# 519_jetson_nano_2GB020000.net
KiCad netlist of a schematic drawn in EAGLE
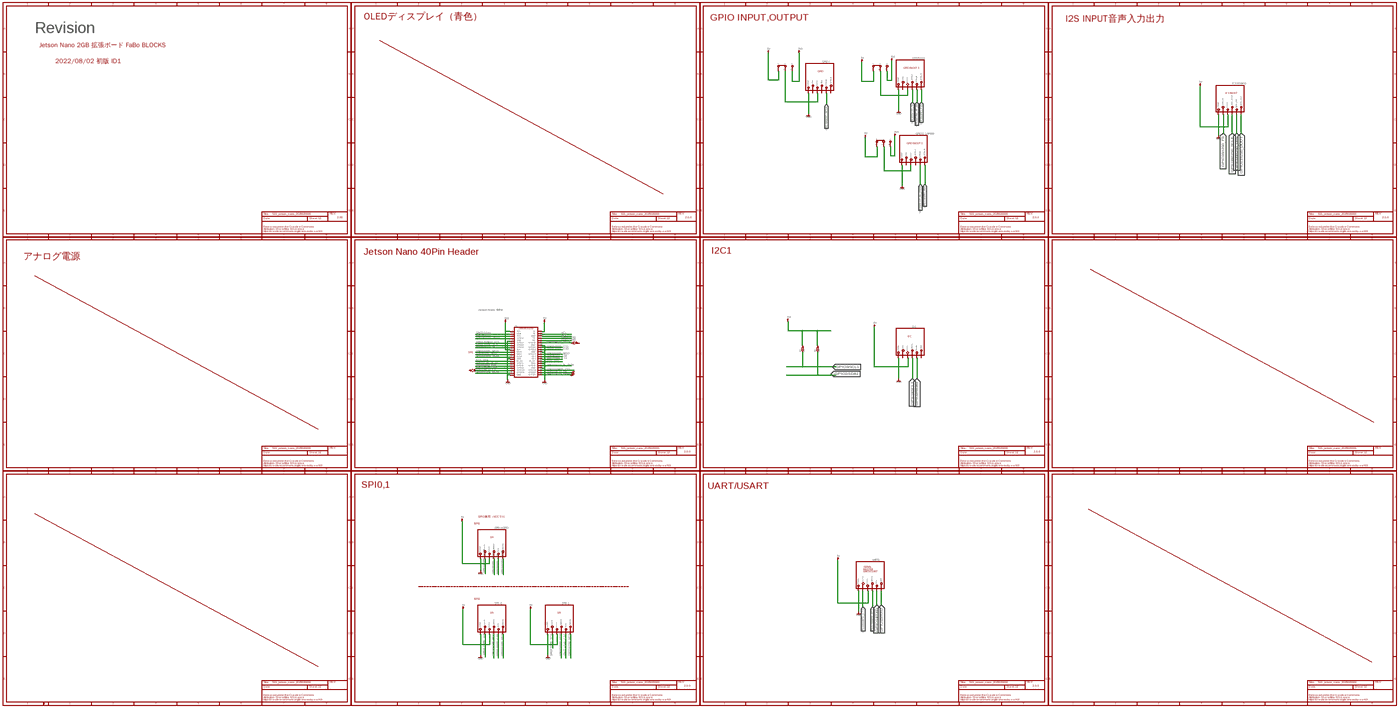
[diagram p0: schematic, sheet 1, overview]
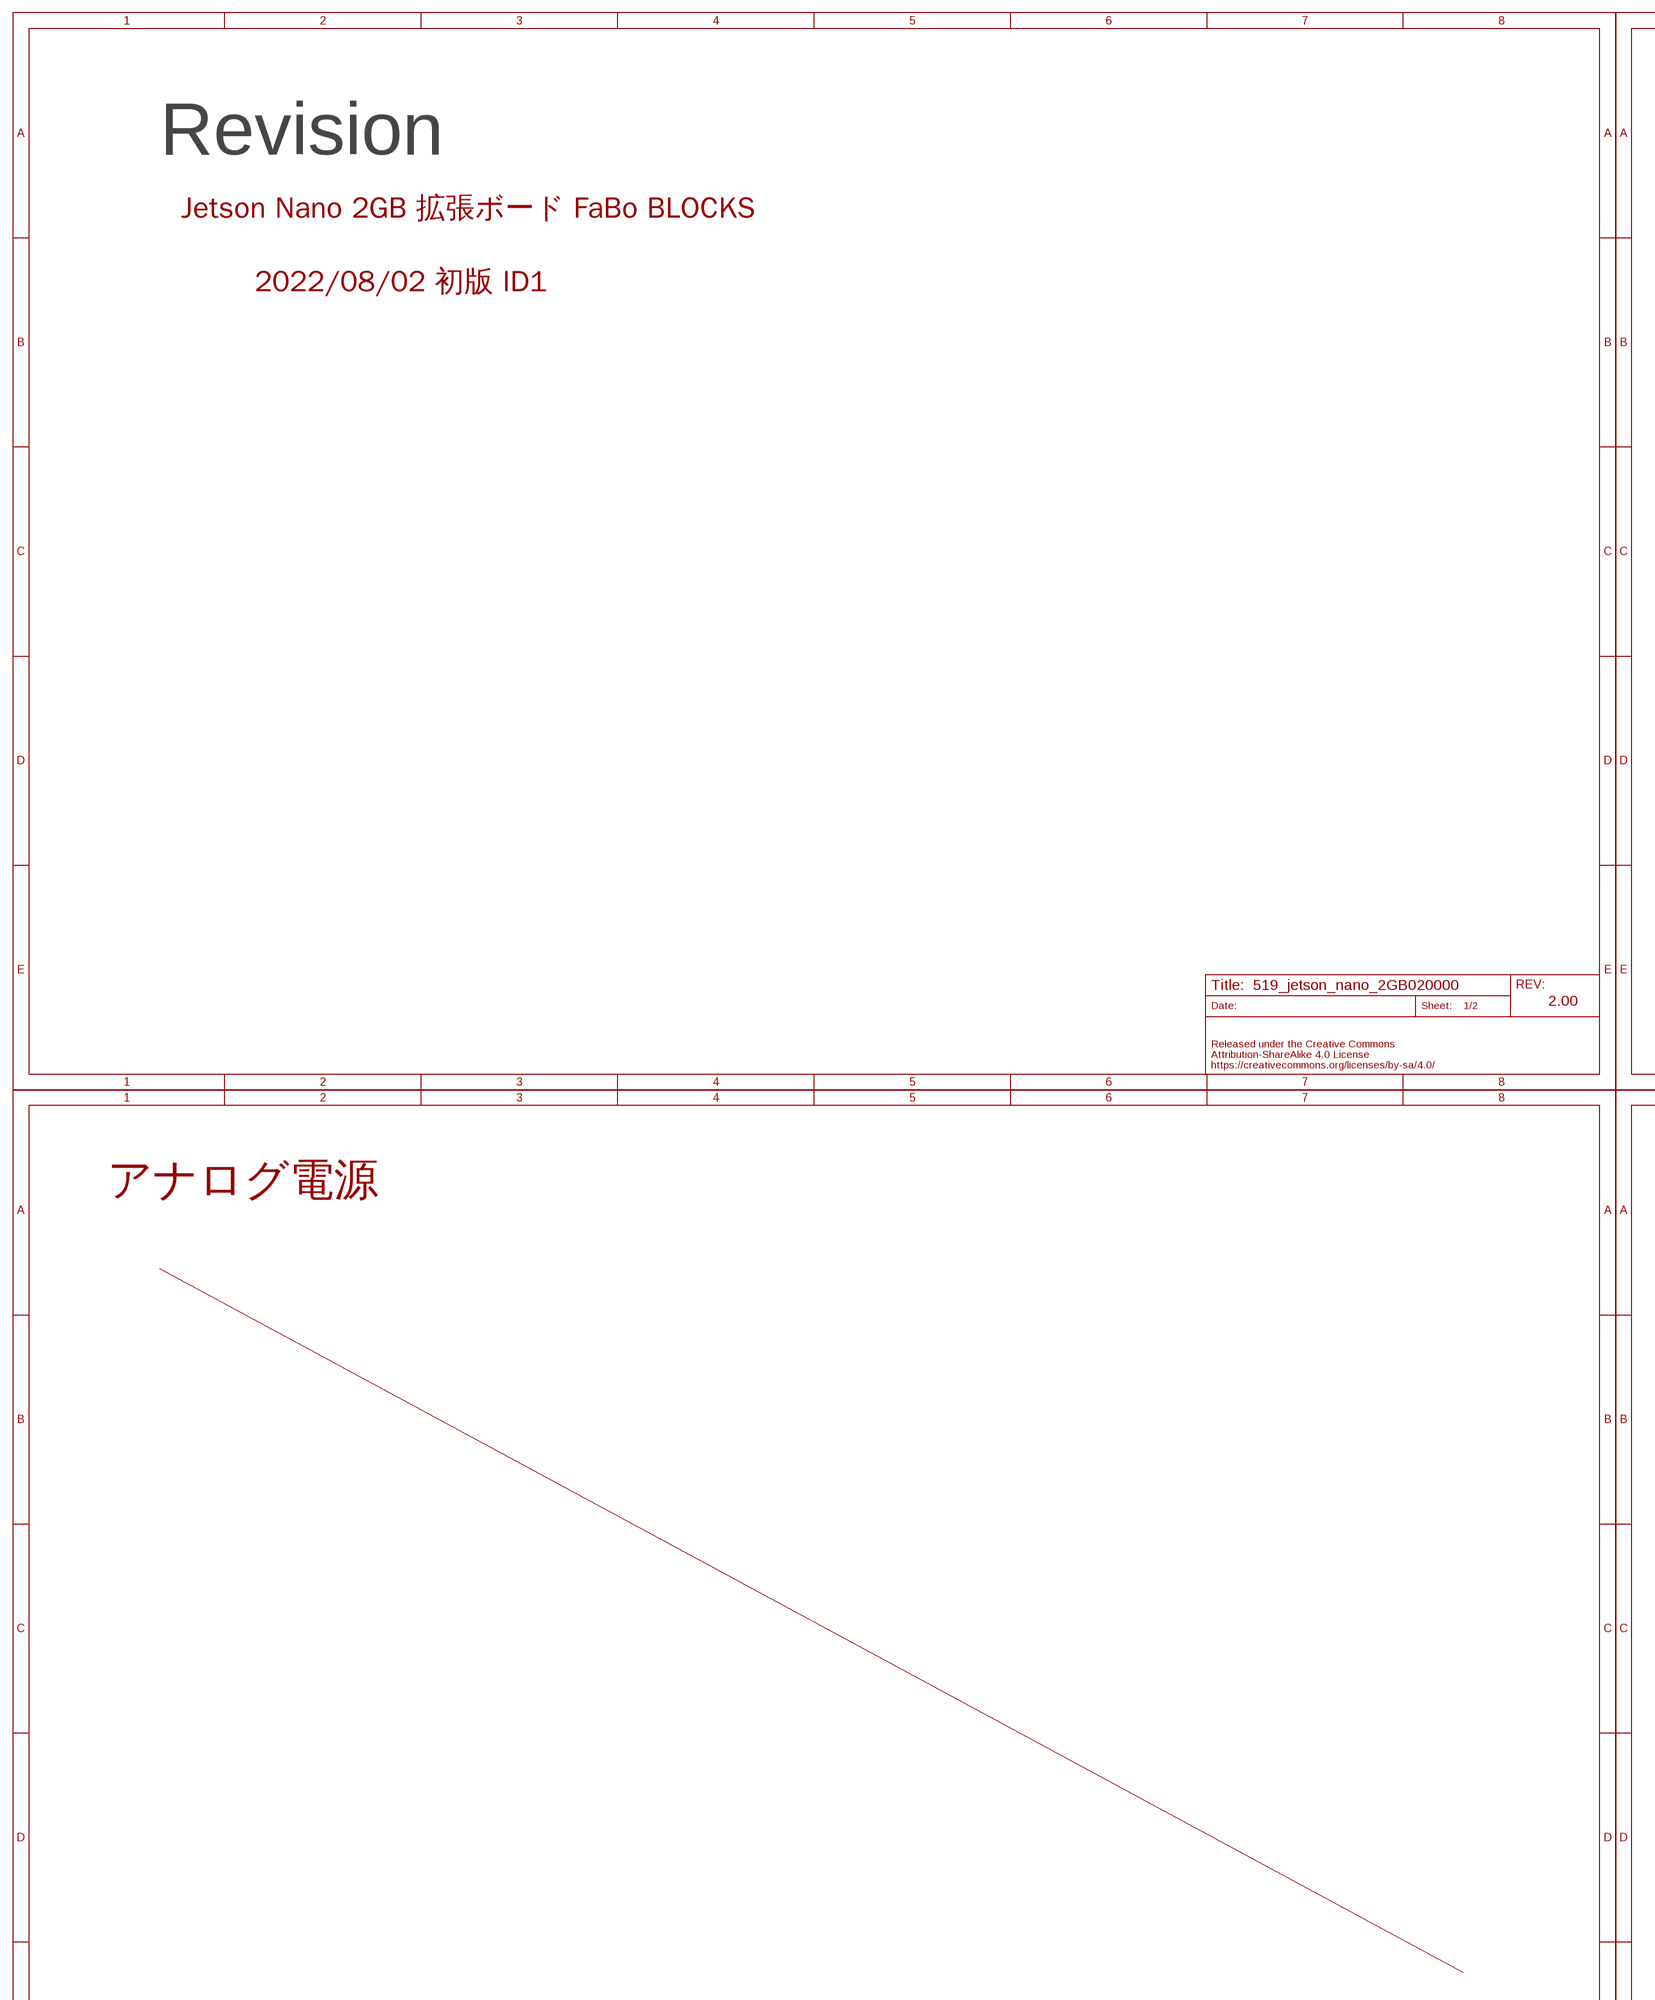
[diagram p1: schematic, sheet 1, part 1 of 6]
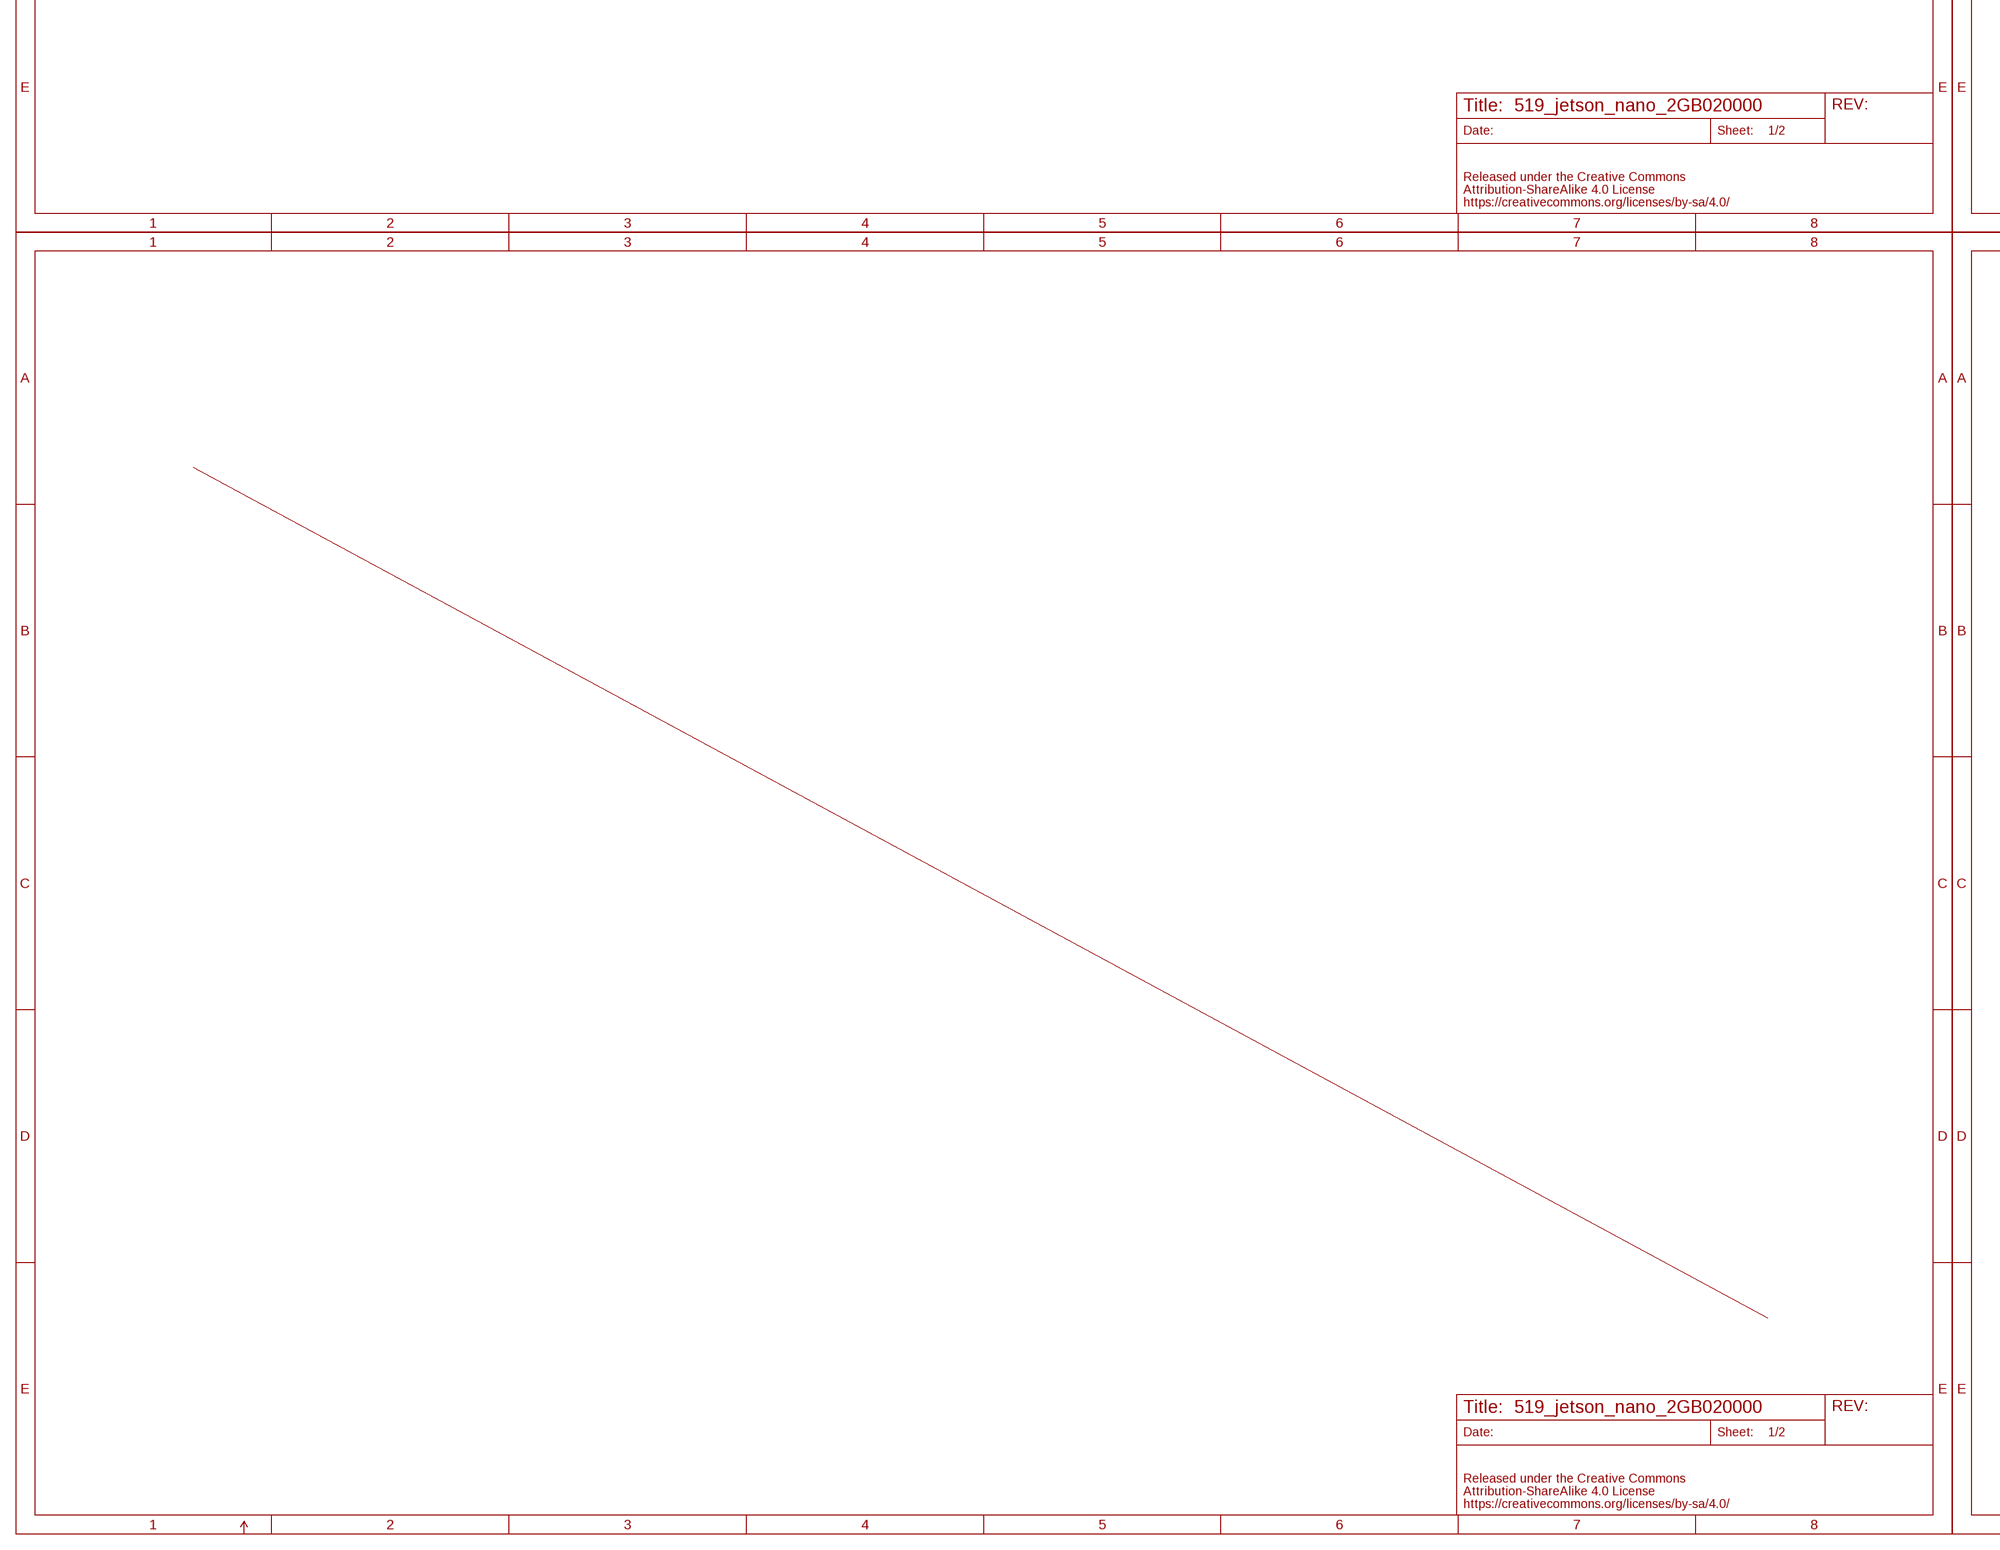
[diagram p2: schematic, sheet 1, part 2 of 6]
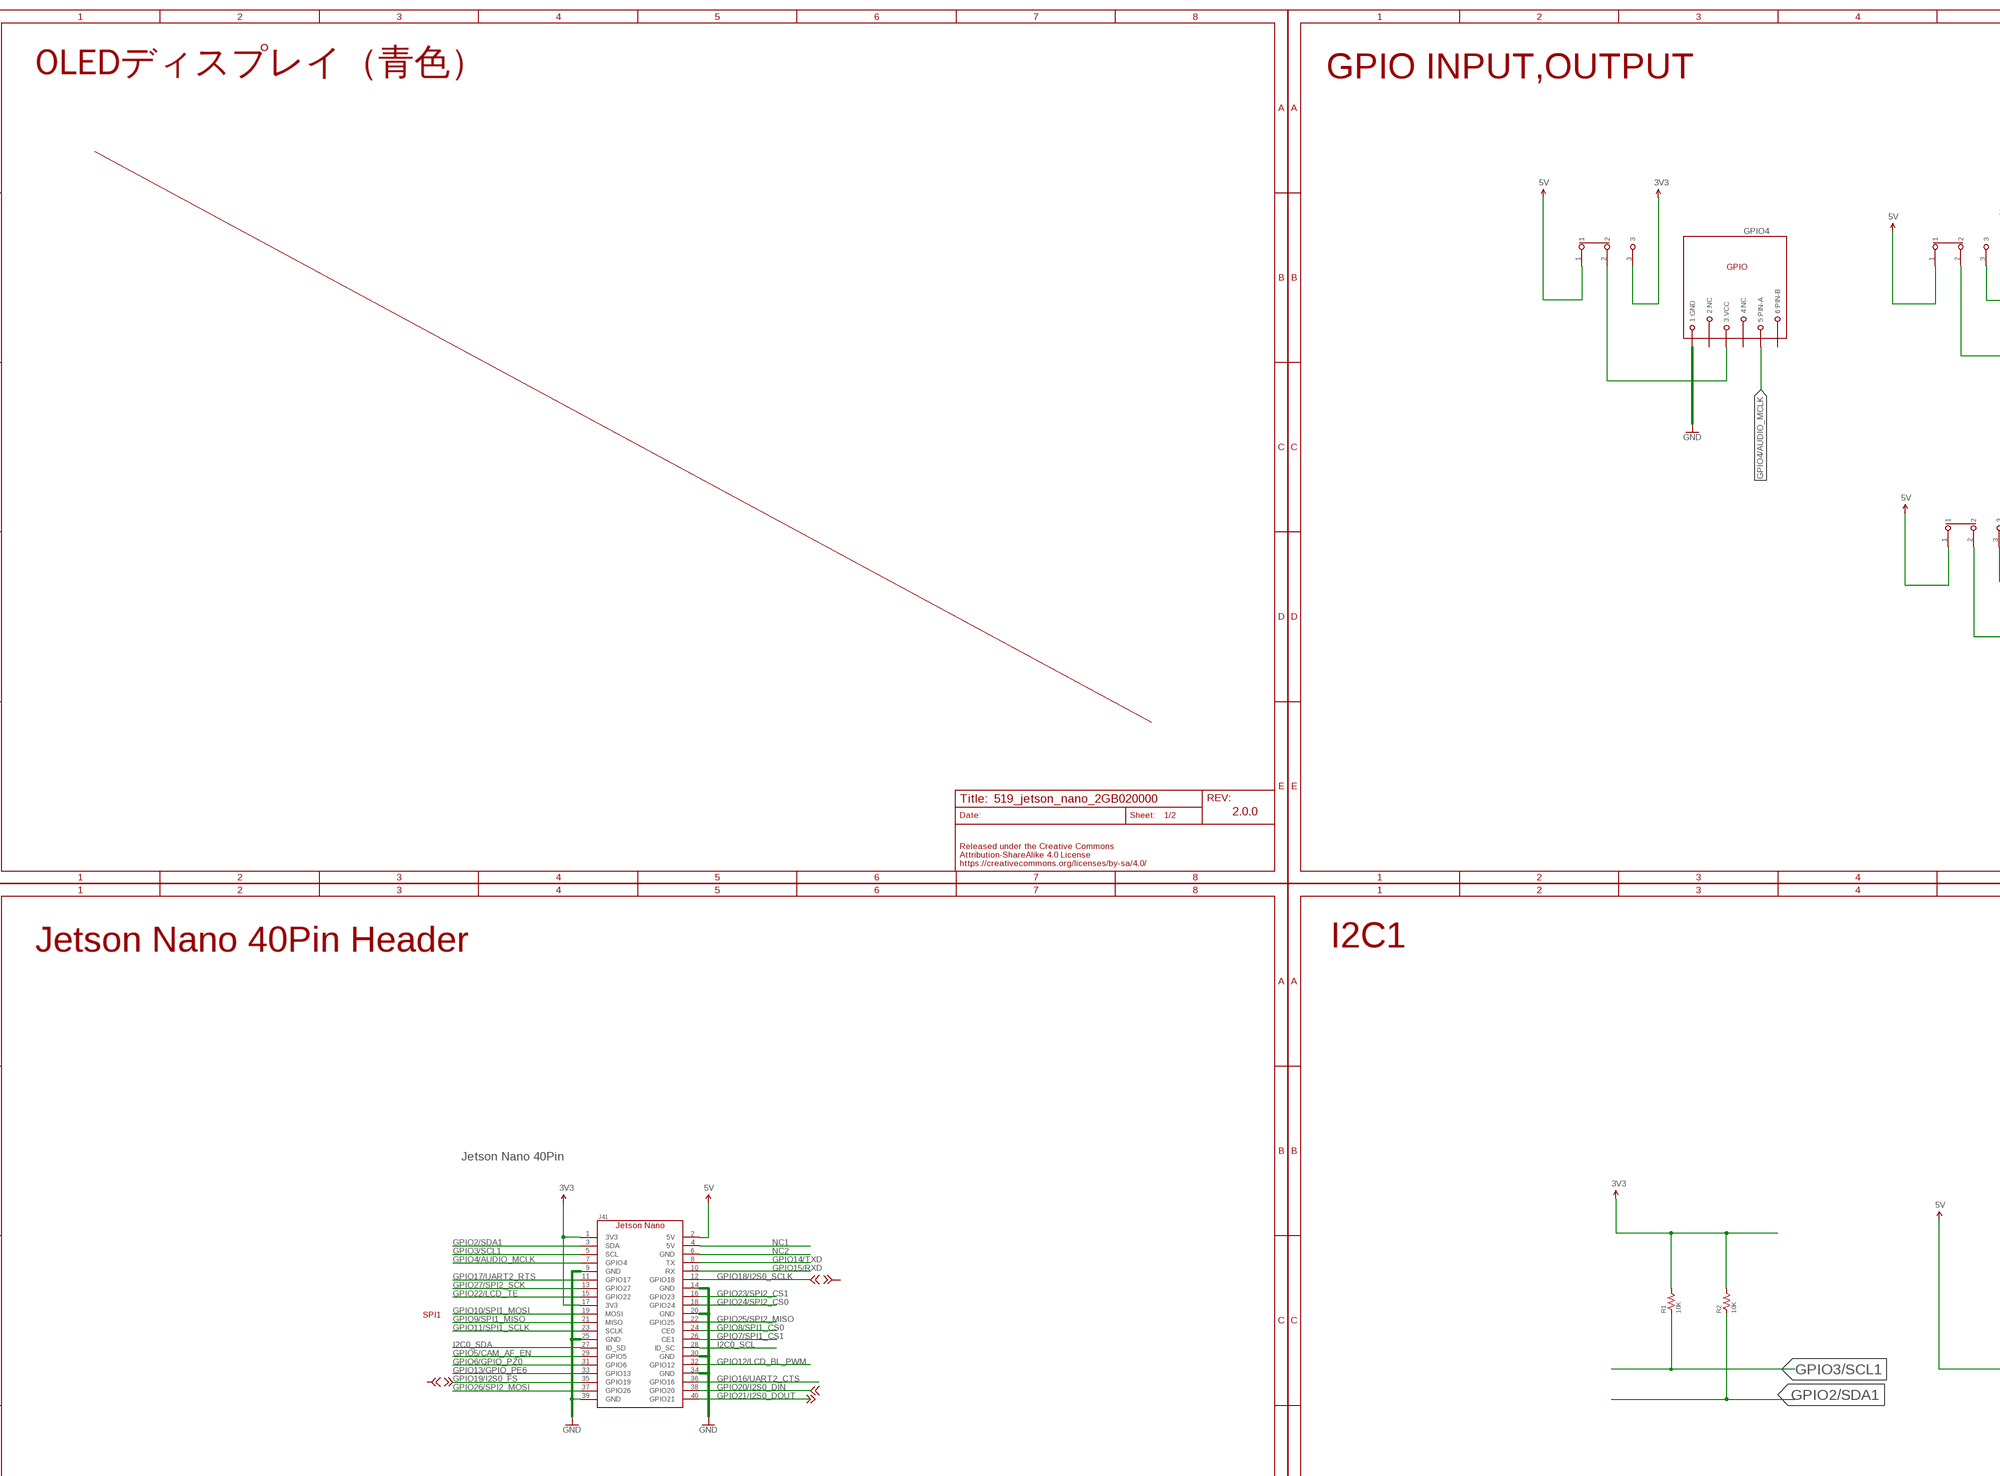
[diagram p3: schematic, sheet 1, part 3 of 6]
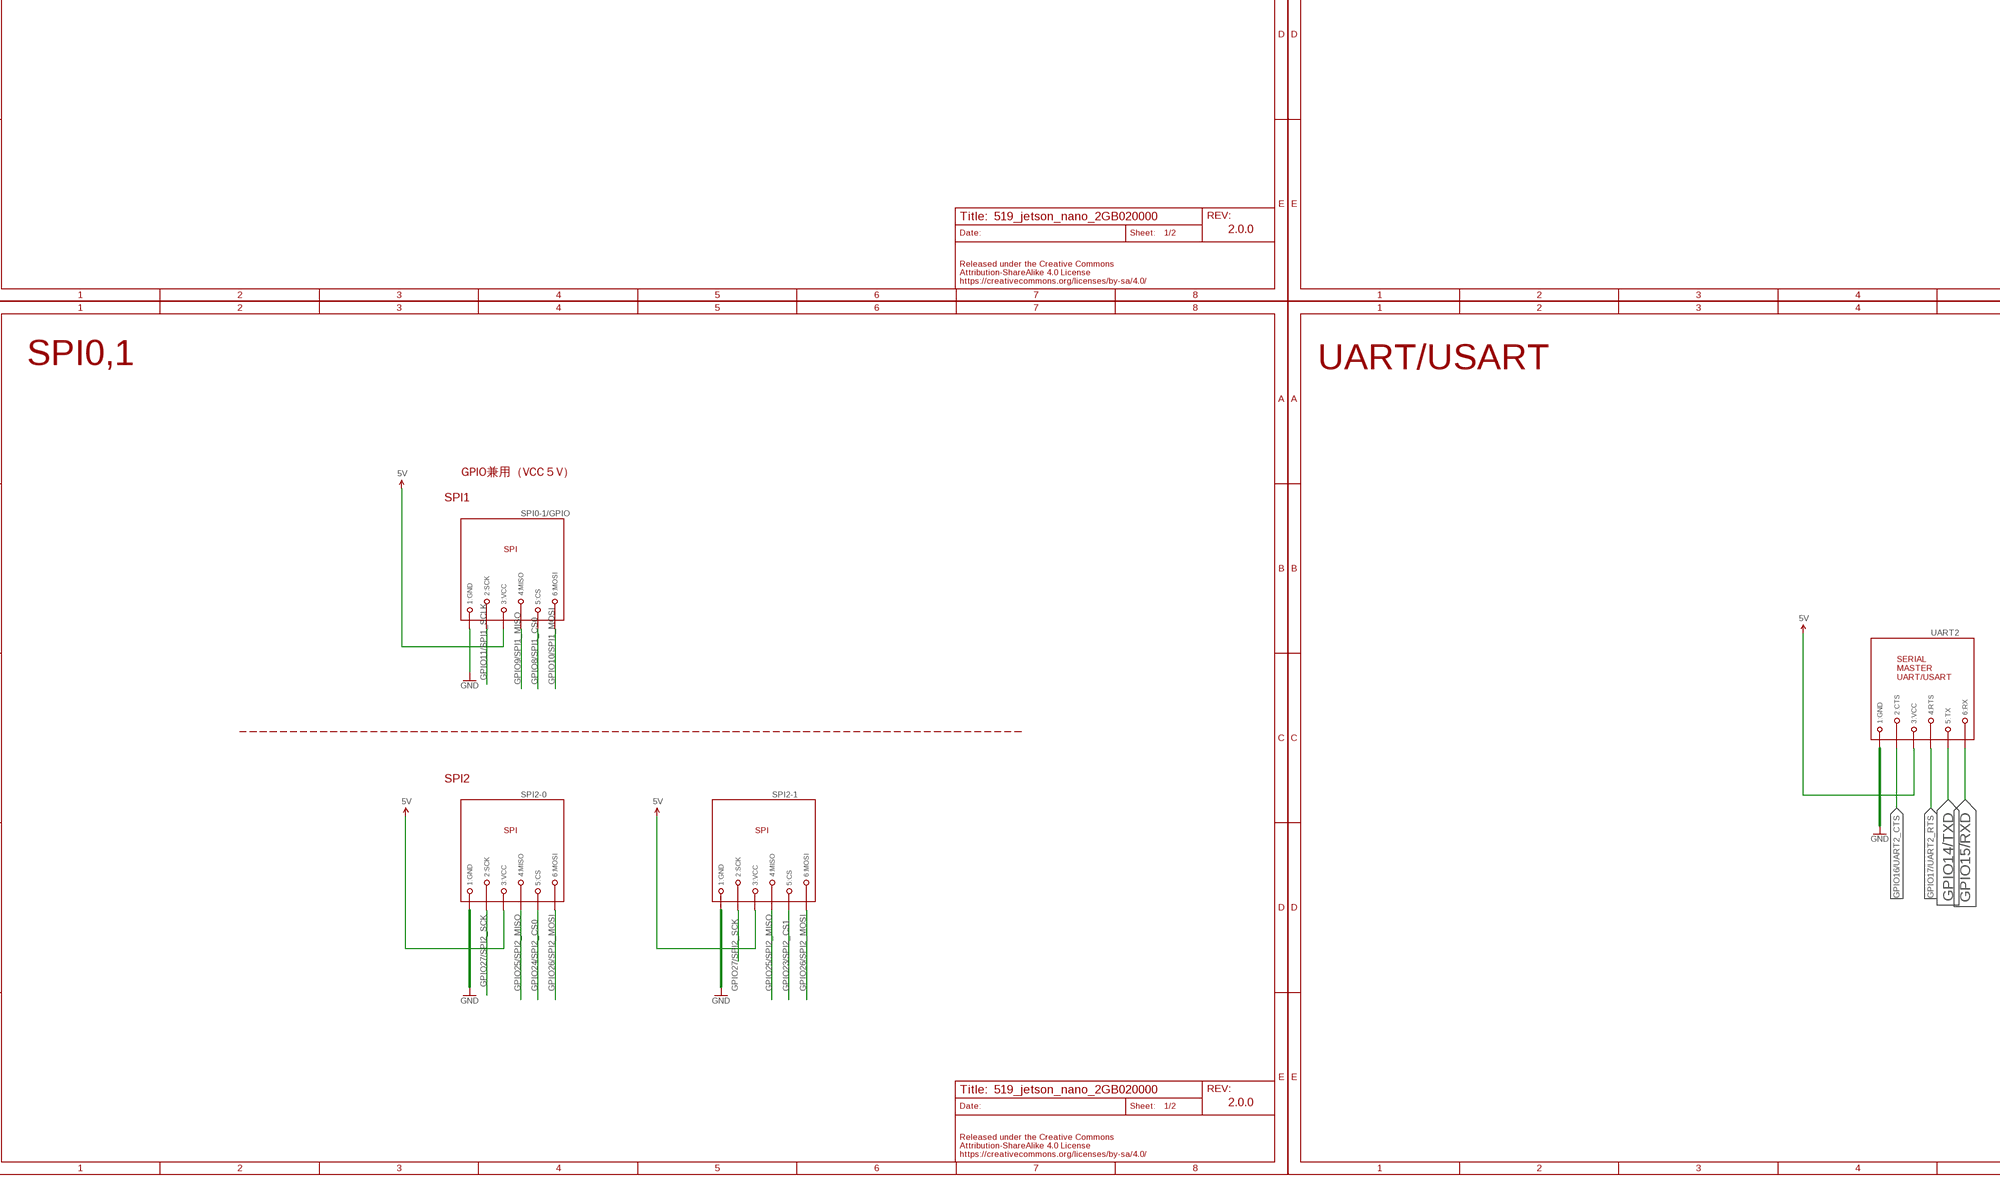
[diagram p4: schematic, sheet 1, part 4 of 6]
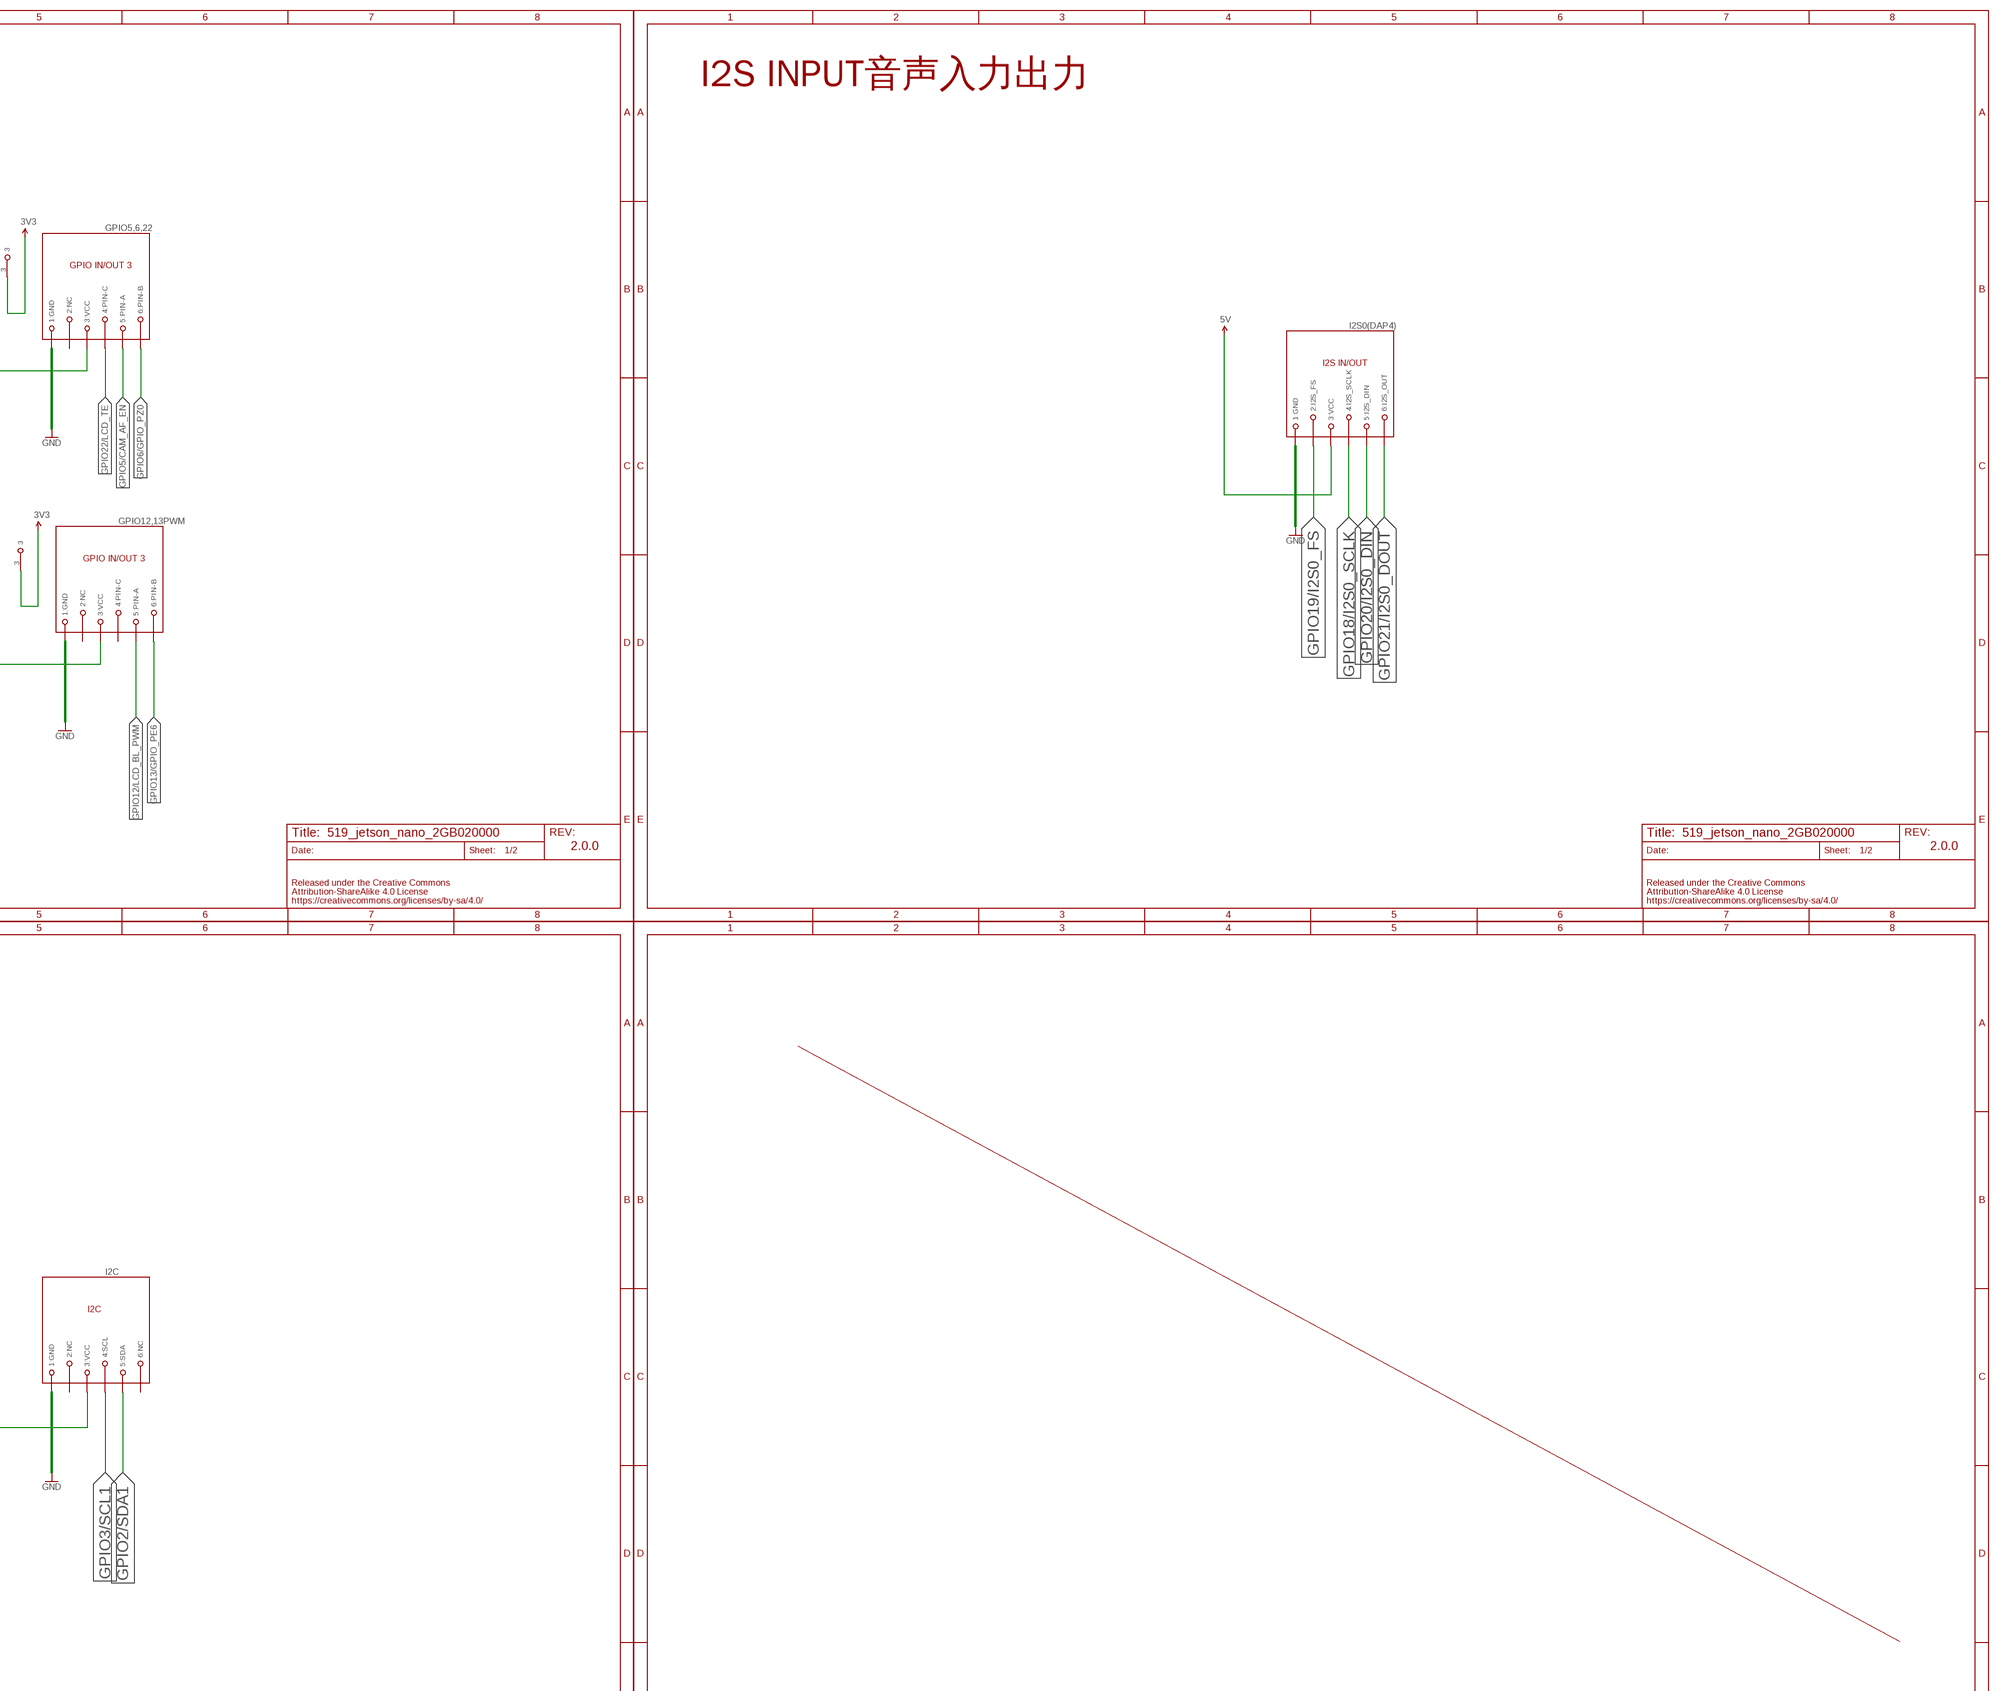
[diagram p5: schematic, sheet 1, part 5 of 6]
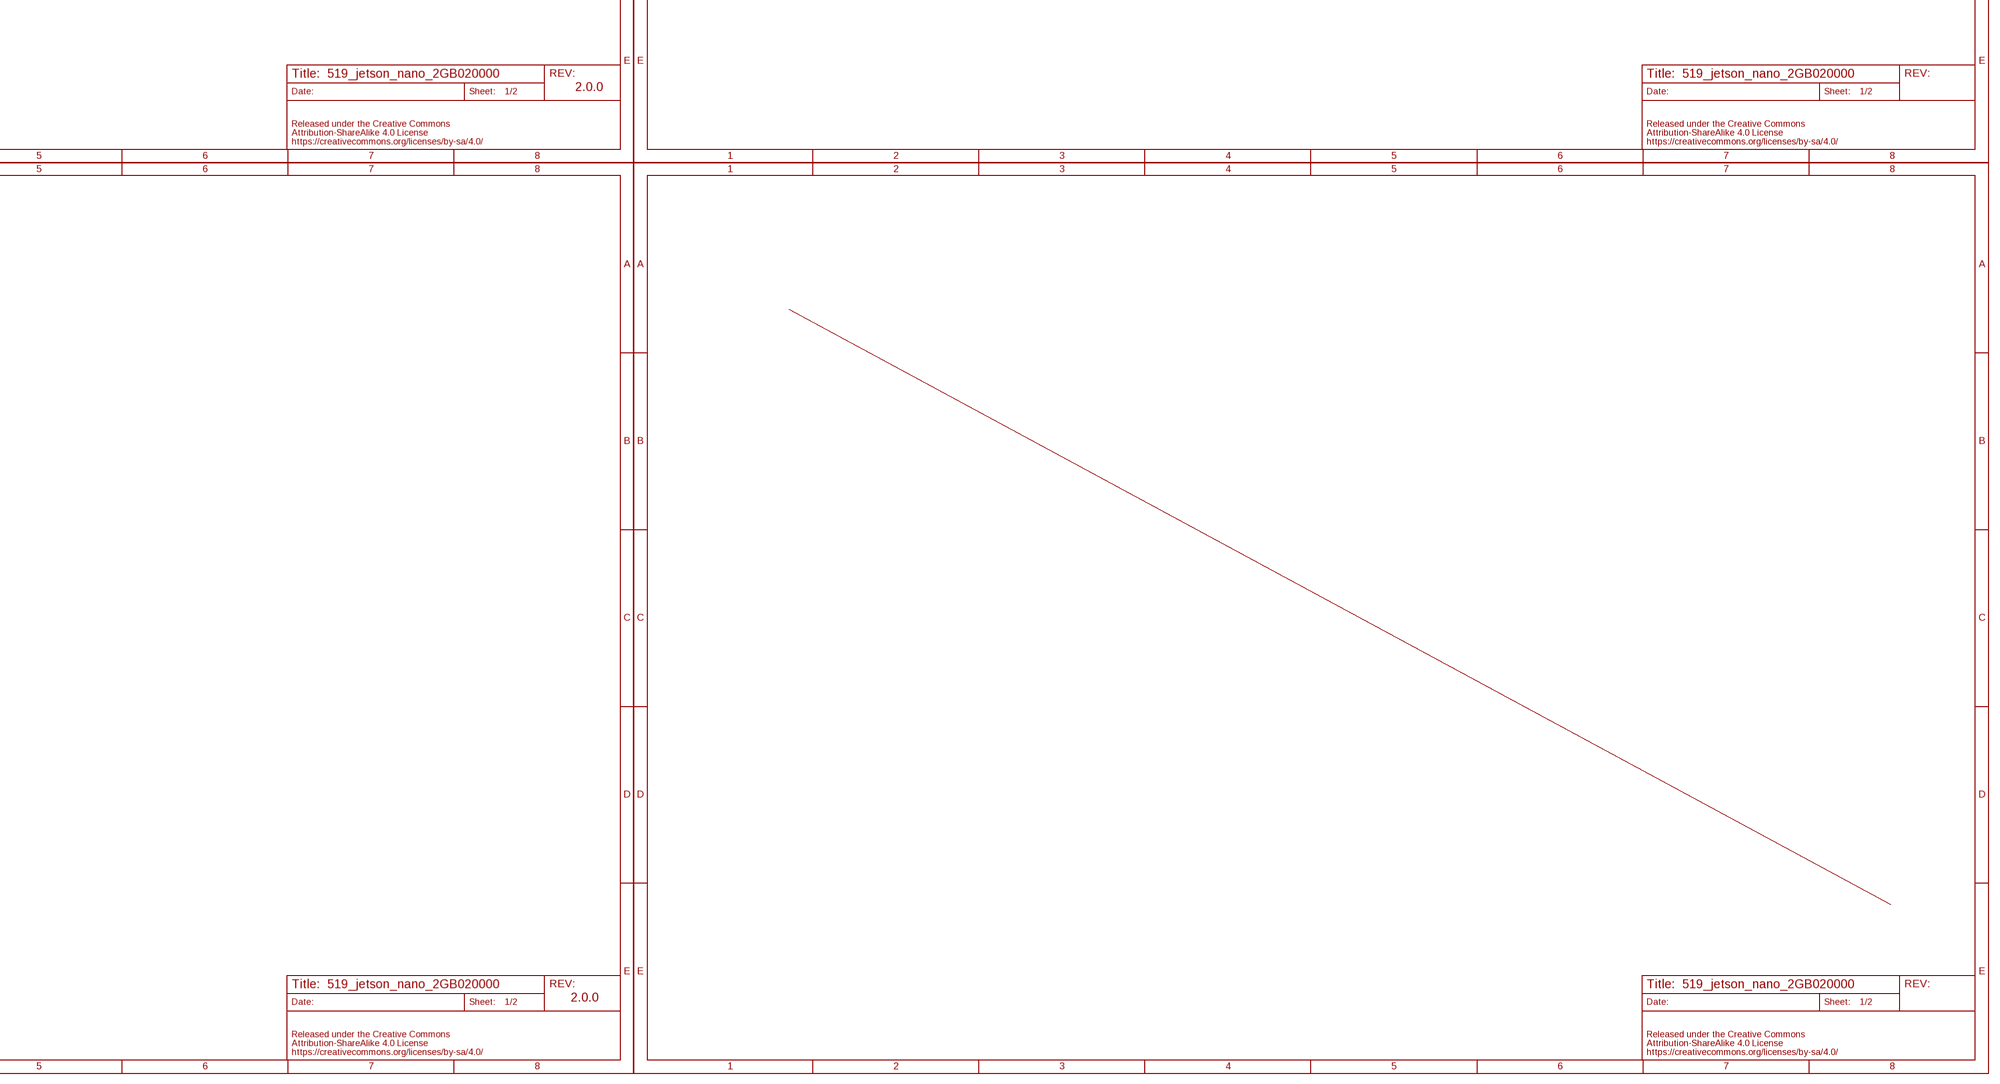
[diagram p6: schematic, sheet 1, part 6 of 6]
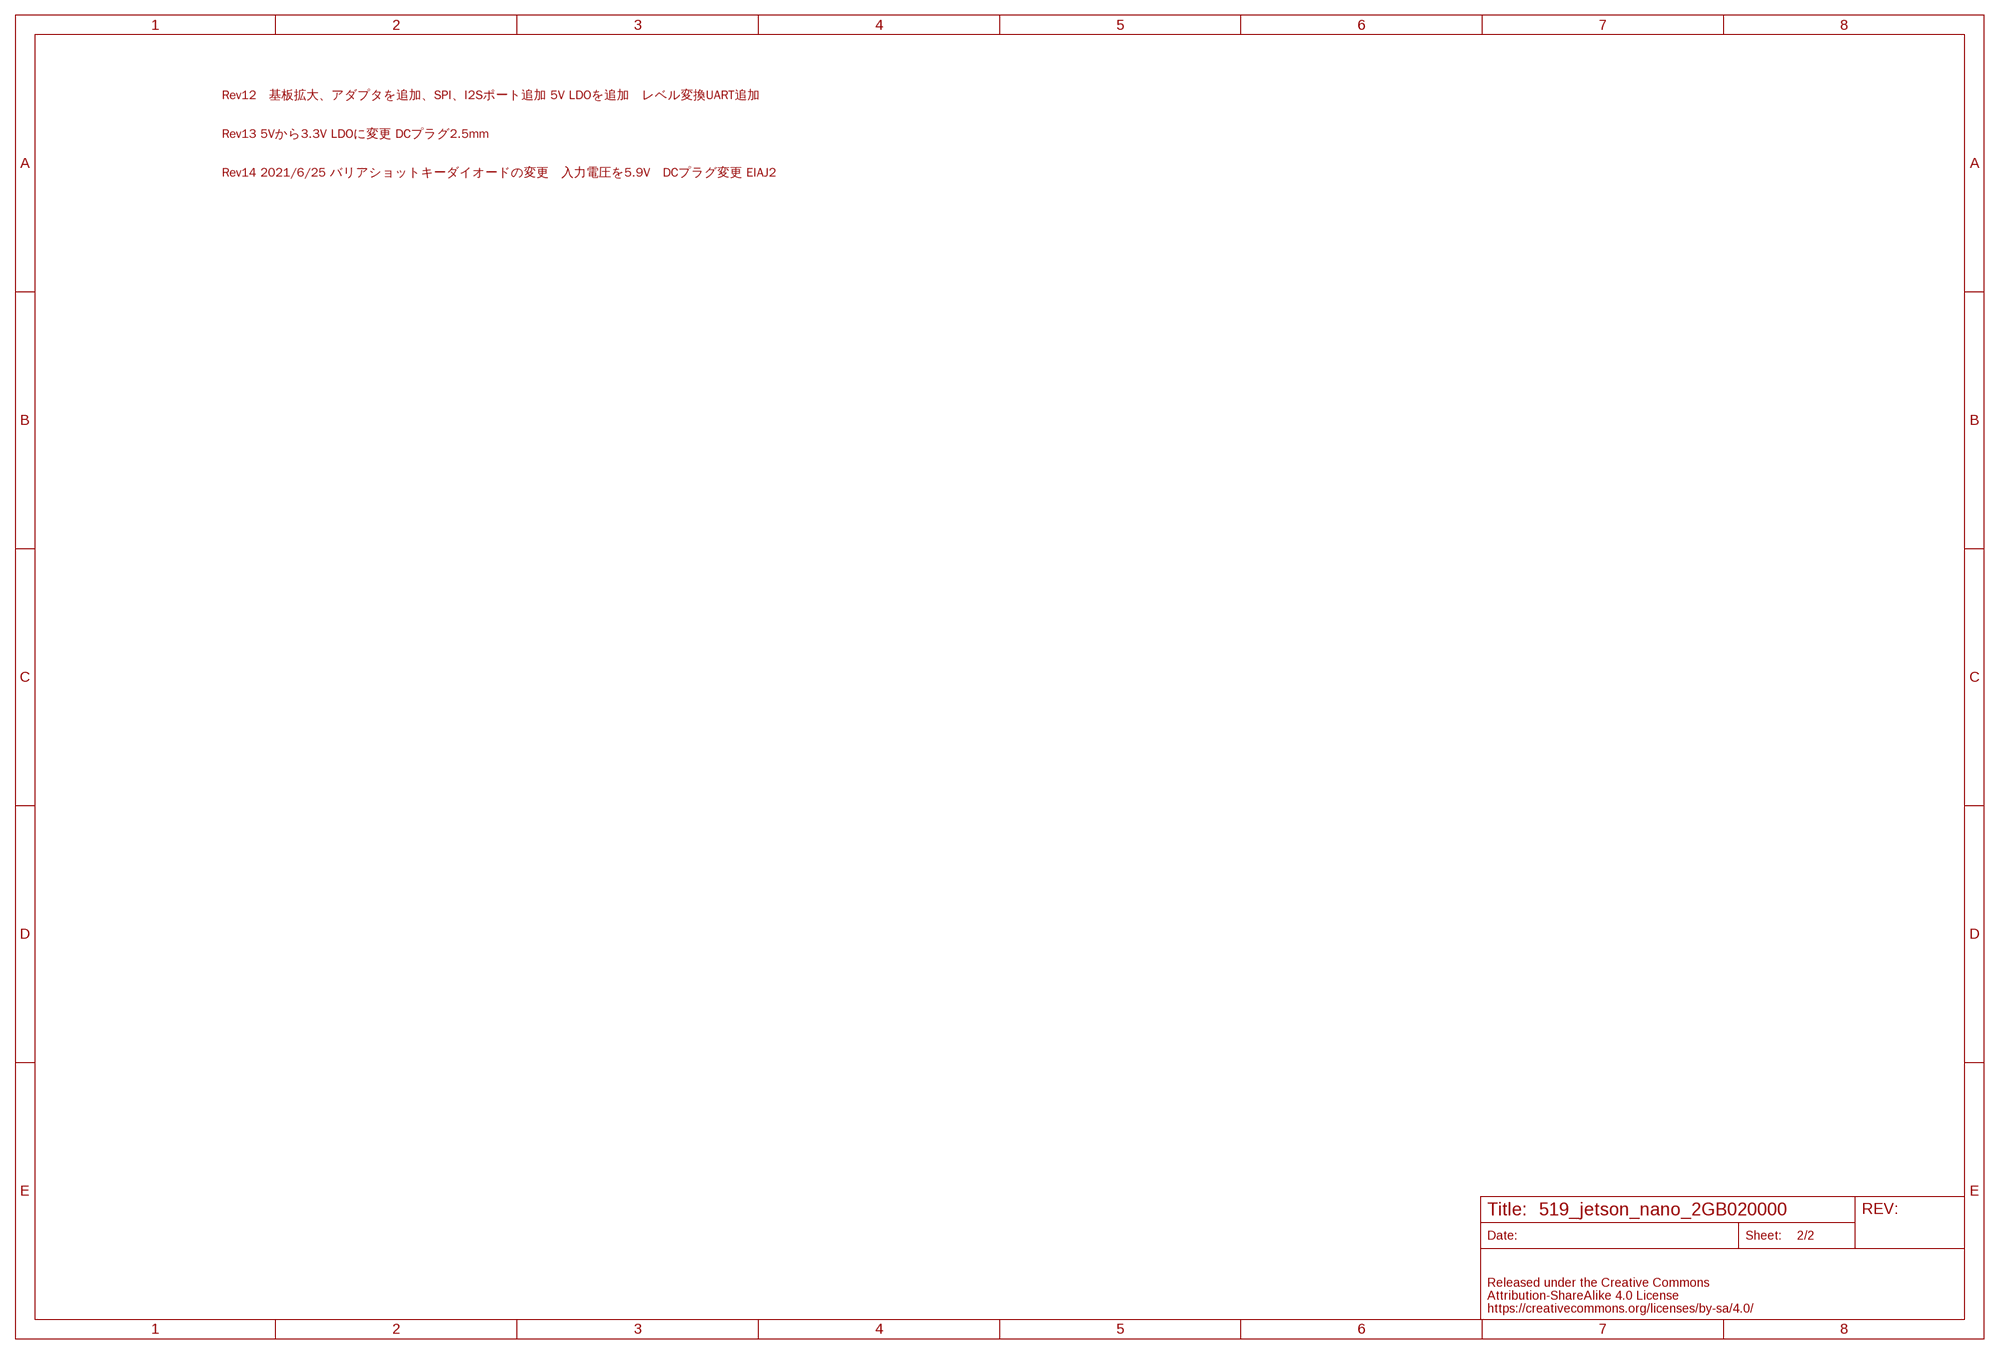
[diagram p7: schematic, sheet 2]

(export (version "E")
  (design (tool "Eeschema 10.0.6"))
  (components
    (comp (ref "GPIO4")
      (value "MODULAR-JACK-6P-RJ11_GPIO")
      (footprint "eagle-import:7002-6PXC-X")
      (libsource (lib "eagle-import") (part "MODULAR-JACK-6P-RJ11_GPIO"))
    )
    (comp (ref "GPIO5,6,22")
      (value "MODULAR-JACK-6P-RJ11_GPIO3")
      (footprint "eagle-import:7002-6PXC-X")
      (libsource (lib "eagle-import") (part "MODULAR-JACK-6P-RJ11_GPIO3"))
    )
    (comp (ref "GPIO12,13PWM")
      (value "MODULAR-JACK-6P-RJ11_GPIO3")
      (footprint "eagle-import:7002-6PXC-X")
      (libsource (lib "eagle-import") (part "MODULAR-JACK-6P-RJ11_GPIO3"))
    )
    (comp (ref "I2C")
      (value "MODULAR-JACK-6P-RJ11_I2C")
      (footprint "eagle-import:7002-6PXC-X")
      (libsource (lib "eagle-import") (part "MODULAR-JACK-6P-RJ11_I2C"))
    )
    (comp (ref "I2S0(DAP4)")
      (value "MODULAR-JACK-6P-RJ11_I2S_MASTER")
      (footprint "eagle-import:7002-6PXC-X")
      (libsource (lib "eagle-import") (part "MODULAR-JACK-6P-RJ11_I2S_MASTER"))
    )
    (comp (ref "J41")
      (value "JETSON_NANOJETSON_NANO_OVERALL")
      (footprint "eagle-import:JETSON_NANO_DEMENTION")
      (libsource (lib "eagle-import") (part "JETSON_NANOJETSON_NANO_OVERALL"))
    )
    (comp (ref "R1")
      (value "10K")
      (footprint "eagle-import:0402")
      (libsource (lib "eagle-import") (part "RESISTOR-0402"))
    )
    (comp (ref "R2")
      (value "10K")
      (footprint "eagle-import:0402")
      (libsource (lib "eagle-import") (part "RESISTOR-0402"))
    )
    (comp (ref "SPI0-1/GPIO")
      (value "MODULAR-JACK-6P-RJ11_SPI")
      (footprint "eagle-import:7002-6PXC-X")
      (libsource (lib "eagle-import") (part "MODULAR-JACK-6P-RJ11_SPI"))
    )
    (comp (ref "SPI2-0")
      (value "MODULAR-JACK-6P-RJ11_SPI")
      (footprint "eagle-import:7002-6PXC-X")
      (libsource (lib "eagle-import") (part "MODULAR-JACK-6P-RJ11_SPI"))
    )
    (comp (ref "SPI2-1")
      (value "MODULAR-JACK-6P-RJ11_SPI")
      (footprint "eagle-import:7002-6PXC-X")
      (libsource (lib "eagle-import") (part "MODULAR-JACK-6P-RJ11_SPI"))
    )
    (comp (ref "U$3")
      (value "SSSS213202")
      (footprint "eagle-import:SSSS213202")
      (libsource (lib "eagle-import") (part "SSSS213202"))
    )
    (comp (ref "U$4")
      (value "SSSS213202")
      (footprint "eagle-import:SSSS213202")
      (libsource (lib "eagle-import") (part "SSSS213202"))
    )
    (comp (ref "U$32")
      (value "SSSS213202")
      (footprint "eagle-import:SSSS213202")
      (libsource (lib "eagle-import") (part "SSSS213202"))
    )
    (comp (ref "UART2")
      (value "MODULAR-JACK-6P-RJ11_SERIAL_M_USART")
      (footprint "eagle-import:7002-6PXC-X")
      (libsource (lib "eagle-import") (part "MODULAR-JACK-6P-RJ11_SERIAL_M_USART"))
    )
  )
  (nets
    (net (code "1") (name "3V3") (class "Default")
      (node (ref "J41") (pin "1") (pinfunction "3V3_1") (pintype "bidirectional"))
      (node (ref "J41") (pin "17") (pinfunction "3V3_17") (pintype "bidirectional"))
      (node (ref "R1") (pin "2") (pinfunction "2_2") (pintype "bidirectional"))
      (node (ref "R2") (pin "2") (pinfunction "2_2") (pintype "bidirectional"))
      (node (ref "U$3") (pin "3") (pinfunction "3_3") (pintype "bidirectional"))
      (node (ref "U$32") (pin "3") (pinfunction "3_3") (pintype "bidirectional"))
      (node (ref "U$4") (pin "3") (pinfunction "3_3") (pintype "bidirectional"))
    )
    (net (code "2") (name "5V") (class "Default")
      (node (ref "I2C") (pin "3") (pinfunction "3:VCC_3") (pintype "power_in"))
      (node (ref "I2S0(DAP4)") (pin "3") (pinfunction "3:VCC_3") (pintype "power_in"))
      (node (ref "J41") (pin "2") (pinfunction "5V_2") (pintype "bidirectional"))
      (node (ref "SPI0-1/GPIO") (pin "3") (pinfunction "3:VCC_3") (pintype "power_in"))
      (node (ref "SPI2-0") (pin "3") (pinfunction "3:VCC_3") (pintype "power_in"))
      (node (ref "SPI2-1") (pin "3") (pinfunction "3:VCC_3") (pintype "power_in"))
      (node (ref "U$3") (pin "1") (pinfunction "1_1") (pintype "bidirectional"))
      (node (ref "U$32") (pin "1") (pinfunction "1_1") (pintype "bidirectional"))
      (node (ref "U$4") (pin "1") (pinfunction "1_1") (pintype "bidirectional"))
      (node (ref "UART2") (pin "3") (pinfunction "3:VCC_3") (pintype "power_in"))
    )
    (net (code "3") (name "GND") (class "Default")
      (node (ref "GPIO12,13PWM") (pin "1") (pinfunction "1:GND_1") (pintype "power_in"))
      (node (ref "GPIO4") (pin "1") (pinfunction "1:GND_1") (pintype "power_in"))
      (node (ref "GPIO5,6,22") (pin "1") (pinfunction "1:GND_1") (pintype "power_in"))
      (node (ref "I2C") (pin "1") (pinfunction "1:GND_1") (pintype "power_in"))
      (node (ref "I2S0(DAP4)") (pin "1") (pinfunction "1:GND_1") (pintype "power_in"))
      (node (ref "J41") (pin "14") (pinfunction "GND_14") (pintype "bidirectional"))
      (node (ref "J41") (pin "20") (pinfunction "GND_20") (pintype "bidirectional"))
      (node (ref "J41") (pin "25") (pinfunction "GND_25") (pintype "bidirectional"))
      (node (ref "J41") (pin "30") (pinfunction "GND_30") (pintype "bidirectional"))
      (node (ref "J41") (pin "34") (pinfunction "GND_34") (pintype "bidirectional"))
      (node (ref "J41") (pin "39") (pinfunction "GND_39") (pintype "bidirectional"))
      (node (ref "J41") (pin "9") (pinfunction "GND_9") (pintype "bidirectional"))
      (node (ref "SPI0-1/GPIO") (pin "1") (pinfunction "1:GND_1") (pintype "power_in"))
      (node (ref "SPI2-0") (pin "1") (pinfunction "1:GND_1") (pintype "power_in"))
      (node (ref "SPI2-1") (pin "1") (pinfunction "1:GND_1") (pintype "power_in"))
      (node (ref "UART2") (pin "1") (pinfunction "1:GND_1") (pintype "power_in"))
    )
    (net (code "4") (name "GPIO2{slash}SDA1") (class "Default")
      (node (ref "I2C") (pin "5") (pinfunction "5:SDA_5") (pintype "open_collector"))
      (node (ref "J41") (pin "3") (pinfunction "SDA_3") (pintype "bidirectional"))
      (node (ref "R2") (pin "1") (pinfunction "1_1") (pintype "bidirectional"))
    )
    (net (code "5") (name "GPIO3{slash}SCL1") (class "Default")
      (node (ref "I2C") (pin "4") (pinfunction "4:SCL_4") (pintype "open_collector"))
      (node (ref "J41") (pin "5") (pinfunction "SCL_5") (pintype "bidirectional"))
      (node (ref "R1") (pin "1") (pinfunction "1_1") (pintype "bidirectional"))
    )
    (net (code "6") (name "GPIO4{slash}AUDIO_MCLK") (class "Default")
      (node (ref "GPIO4") (pin "5") (pinfunction "5:PIN-A_5") (pintype "bidirectional"))
      (node (ref "J41") (pin "7") (pinfunction "GPIO4_7") (pintype "bidirectional"))
    )
    (net (code "7") (name "GPIO5{slash}CAM_AF_EN") (class "Default")
      (node (ref "GPIO5,6,22") (pin "5") (pinfunction "5:PIN-A_5") (pintype "bidirectional"))
      (node (ref "J41") (pin "29") (pinfunction "GPIO5_29") (pintype "bidirectional"))
    )
    (net (code "8") (name "GPIO6{slash}GPIO_PZ0") (class "Default")
      (node (ref "GPIO5,6,22") (pin "6") (pinfunction "6:PIN-B_6") (pintype "bidirectional"))
      (node (ref "J41") (pin "31") (pinfunction "GPIO6_31") (pintype "bidirectional"))
    )
    (net (code "9") (name "GPIO7{slash}SPI1_CS1") (class "Default")
      (node (ref "J41") (pin "26") (pinfunction "CE1_26") (pintype "bidirectional"))
    )
    (net (code "10") (name "GPIO8{slash}SPI1_CS0") (class "Default")
      (node (ref "J41") (pin "24") (pinfunction "CE0_24") (pintype "bidirectional"))
      (node (ref "SPI0-1/GPIO") (pin "5") (pinfunction "5:CS_5") (pintype "open_collector"))
    )
    (net (code "11") (name "GPIO9{slash}SPI1_MISO") (class "Default")
      (node (ref "J41") (pin "21") (pinfunction "MISO_21") (pintype "bidirectional"))
      (node (ref "SPI0-1/GPIO") (pin "4") (pinfunction "4:MISO_4") (pintype "open_collector"))
    )
    (net (code "12") (name "GPIO10{slash}SPI1_MOSI") (class "Default")
      (node (ref "J41") (pin "19") (pinfunction "MOSI_19") (pintype "bidirectional"))
      (node (ref "SPI0-1/GPIO") (pin "6") (pinfunction "6:MOSI_6") (pintype "open_collector"))
    )
    (net (code "13") (name "GPIO11{slash}SPI1_SCLK") (class "Default")
      (node (ref "J41") (pin "23") (pinfunction "SCLK_23") (pintype "bidirectional"))
      (node (ref "SPI0-1/GPIO") (pin "2") (pinfunction "2:SCK_2") (pintype "open_collector"))
    )
    (net (code "14") (name "GPIO12{slash}LCD_BL_PWM") (class "Default")
      (node (ref "GPIO12,13PWM") (pin "5") (pinfunction "5:PIN-A_5") (pintype "bidirectional"))
      (node (ref "J41") (pin "32") (pinfunction "GPIO12_32") (pintype "bidirectional"))
    )
    (net (code "15") (name "GPIO13{slash}GPIO_PE6") (class "Default")
      (node (ref "GPIO12,13PWM") (pin "6") (pinfunction "6:PIN-B_6") (pintype "bidirectional"))
      (node (ref "J41") (pin "33") (pinfunction "GPIO13_33") (pintype "bidirectional"))
    )
    (net (code "16") (name "GPIO14{slash}TXD") (class "Default")
      (node (ref "J41") (pin "8") (pinfunction "TX_8") (pintype "bidirectional"))
      (node (ref "UART2") (pin "5") (pinfunction "5:TX_5") (pintype "output"))
    )
    (net (code "17") (name "GPIO15{slash}RXD") (class "Default")
      (node (ref "J41") (pin "10") (pinfunction "RX_10") (pintype "bidirectional"))
      (node (ref "UART2") (pin "6") (pinfunction "6:RX_6") (pintype "input"))
    )
    (net (code "18") (name "GPIO16{slash}UART2_CTS") (class "Default")
      (node (ref "J41") (pin "36") (pinfunction "GPIO16_36") (pintype "bidirectional"))
      (node (ref "UART2") (pin "2") (pinfunction "2:CTS_2") (pintype "bidirectional"))
    )
    (net (code "19") (name "GPIO17{slash}UART2_RTS") (class "Default")
      (node (ref "J41") (pin "11") (pinfunction "GPIO17_11") (pintype "bidirectional"))
      (node (ref "UART2") (pin "4") (pinfunction "4:RTS_4") (pintype "bidirectional"))
    )
    (net (code "20") (name "GPIO18{slash}I2S0_SCLK") (class "Default")
      (node (ref "I2S0(DAP4)") (pin "4") (pinfunction "4:I2S_SCLK_4") (pintype "open_collector"))
      (node (ref "J41") (pin "12") (pinfunction "GPIO18_12") (pintype "bidirectional"))
    )
    (net (code "21") (name "GPIO19{slash}I2S0_FS") (class "Default")
      (node (ref "I2S0(DAP4)") (pin "2") (pinfunction "2:I2S_FS_2") (pintype "input"))
      (node (ref "J41") (pin "35") (pinfunction "GPIO19_35") (pintype "bidirectional"))
    )
    (net (code "22") (name "GPIO20{slash}I2S0_DIN") (class "Default")
      (node (ref "I2S0(DAP4)") (pin "5") (pinfunction "5:I2S_DIN_5") (pintype "input"))
      (node (ref "J41") (pin "38") (pinfunction "GPIO20_38") (pintype "bidirectional"))
    )
    (net (code "23") (name "GPIO21{slash}I2S0_DOUT") (class "Default")
      (node (ref "I2S0(DAP4)") (pin "6") (pinfunction "6:I2S_OUT_6") (pintype "output"))
      (node (ref "J41") (pin "40") (pinfunction "GPIO21_40") (pintype "bidirectional"))
    )
    (net (code "24") (name "GPIO22{slash}LCD_TE") (class "Default")
      (node (ref "GPIO5,6,22") (pin "4") (pinfunction "4:PIN-C_4") (pintype "bidirectional"))
      (node (ref "J41") (pin "15") (pinfunction "GPIO22_15") (pintype "bidirectional"))
    )
    (net (code "25") (name "GPIO23{slash}SPI2_CS1") (class "Default")
      (node (ref "J41") (pin "16") (pinfunction "GPIO23_16") (pintype "bidirectional"))
      (node (ref "SPI2-1") (pin "5") (pinfunction "5:CS_5") (pintype "open_collector"))
    )
    (net (code "26") (name "GPIO24{slash}SPI2_CS0") (class "Default")
      (node (ref "J41") (pin "18") (pinfunction "GPIO24_18") (pintype "bidirectional"))
      (node (ref "SPI2-0") (pin "5") (pinfunction "5:CS_5") (pintype "open_collector"))
    )
    (net (code "27") (name "GPIO25{slash}SPI2_MISO") (class "Default")
      (node (ref "J41") (pin "22") (pinfunction "GPIO25_22") (pintype "bidirectional"))
      (node (ref "SPI2-0") (pin "4") (pinfunction "4:MISO_4") (pintype "open_collector"))
      (node (ref "SPI2-1") (pin "4") (pinfunction "4:MISO_4") (pintype "open_collector"))
    )
    (net (code "28") (name "GPIO26{slash}SPI2_MOSI") (class "Default")
      (node (ref "J41") (pin "37") (pinfunction "GPIO26_37") (pintype "bidirectional"))
      (node (ref "SPI2-0") (pin "6") (pinfunction "6:MOSI_6") (pintype "open_collector"))
      (node (ref "SPI2-1") (pin "6") (pinfunction "6:MOSI_6") (pintype "open_collector"))
    )
    (net (code "29") (name "GPIO27{slash}SPI2_SCK") (class "Default")
      (node (ref "J41") (pin "13") (pinfunction "GPIO27_13") (pintype "bidirectional"))
      (node (ref "SPI2-0") (pin "2") (pinfunction "2:SCK_2") (pintype "open_collector"))
      (node (ref "SPI2-1") (pin "2") (pinfunction "2:SCK_2") (pintype "open_collector"))
    )
    (net (code "30") (name "I2C0_SCL") (class "Default")
      (node (ref "J41") (pin "28") (pinfunction "ID_SC_28") (pintype "bidirectional"))
    )
    (net (code "31") (name "I2C0_SDA") (class "Default")
      (node (ref "J41") (pin "27") (pinfunction "ID_SD_27") (pintype "bidirectional"))
    )
    (net (code "32") (name "NC1") (class "Default")
      (node (ref "J41") (pin "4") (pinfunction "5V_4") (pintype "bidirectional"))
    )
    (net (code "33") (name "NC2") (class "Default")
      (node (ref "J41") (pin "6") (pinfunction "GND_6") (pintype "bidirectional"))
    )
    (net (code "34") (name "Net-(GPIO4-3:VCC)") (class "Default")
      (node (ref "GPIO4") (pin "3") (pinfunction "3:VCC_3") (pintype "power_in"))
      (node (ref "U$32") (pin "2") (pinfunction "2_2") (pintype "bidirectional"))
    )
    (net (code "35") (name "Net-(GPIO5,6,22-3:VCC)") (class "Default")
      (node (ref "GPIO5,6,22") (pin "3") (pinfunction "3:VCC_3") (pintype "power_in"))
      (node (ref "U$3") (pin "2") (pinfunction "2_2") (pintype "bidirectional"))
    )
    (net (code "36") (name "Net-(GPIO12,13PWM-3:VCC)") (class "Default")
      (node (ref "GPIO12,13PWM") (pin "3") (pinfunction "3:VCC_3") (pintype "power_in"))
      (node (ref "U$4") (pin "2") (pinfunction "2_2") (pintype "bidirectional"))
    )
    (net (code "37") (name "unconnected-(GPIO4-2:NC-Pad2)") (class "Default")
      (node (ref "GPIO4") (pin "2") (pinfunction "2:NC_2") (pintype "no_connect"))
    )
    (net (code "38") (name "unconnected-(GPIO4-4:NC-Pad4)") (class "Default")
      (node (ref "GPIO4") (pin "4") (pinfunction "4:NC_4") (pintype "no_connect"))
    )
    (net (code "39") (name "unconnected-(GPIO4-6:PIN-B-Pad6)") (class "Default")
      (node (ref "GPIO4") (pin "6") (pinfunction "6:PIN-B_6") (pintype "bidirectional"))
    )
    (net (code "40") (name "unconnected-(GPIO5,6,22-2:NC-Pad2)") (class "Default")
      (node (ref "GPIO5,6,22") (pin "2") (pinfunction "2:NC_2") (pintype "no_connect"))
    )
    (net (code "41") (name "unconnected-(GPIO12,13PWM-2:NC-Pad2)") (class "Default")
      (node (ref "GPIO12,13PWM") (pin "2") (pinfunction "2:NC_2") (pintype "no_connect"))
    )
    (net (code "42") (name "unconnected-(GPIO12,13PWM-4:PIN-C-Pad4)") (class "Default")
      (node (ref "GPIO12,13PWM") (pin "4") (pinfunction "4:PIN-C_4") (pintype "bidirectional"))
    )
    (net (code "43") (name "unconnected-(I2C-2:NC-Pad2)") (class "Default")
      (node (ref "I2C") (pin "2") (pinfunction "2:NC_2") (pintype "no_connect"))
    )
    (net (code "44") (name "unconnected-(I2C-6:NC-Pad6)") (class "Default")
      (node (ref "I2C") (pin "6") (pinfunction "6:NC_6") (pintype "no_connect"))
    )
  )
)
